# Precision_ATMega32U4.net
KiCad netlist of a schematic drawn in EAGLE
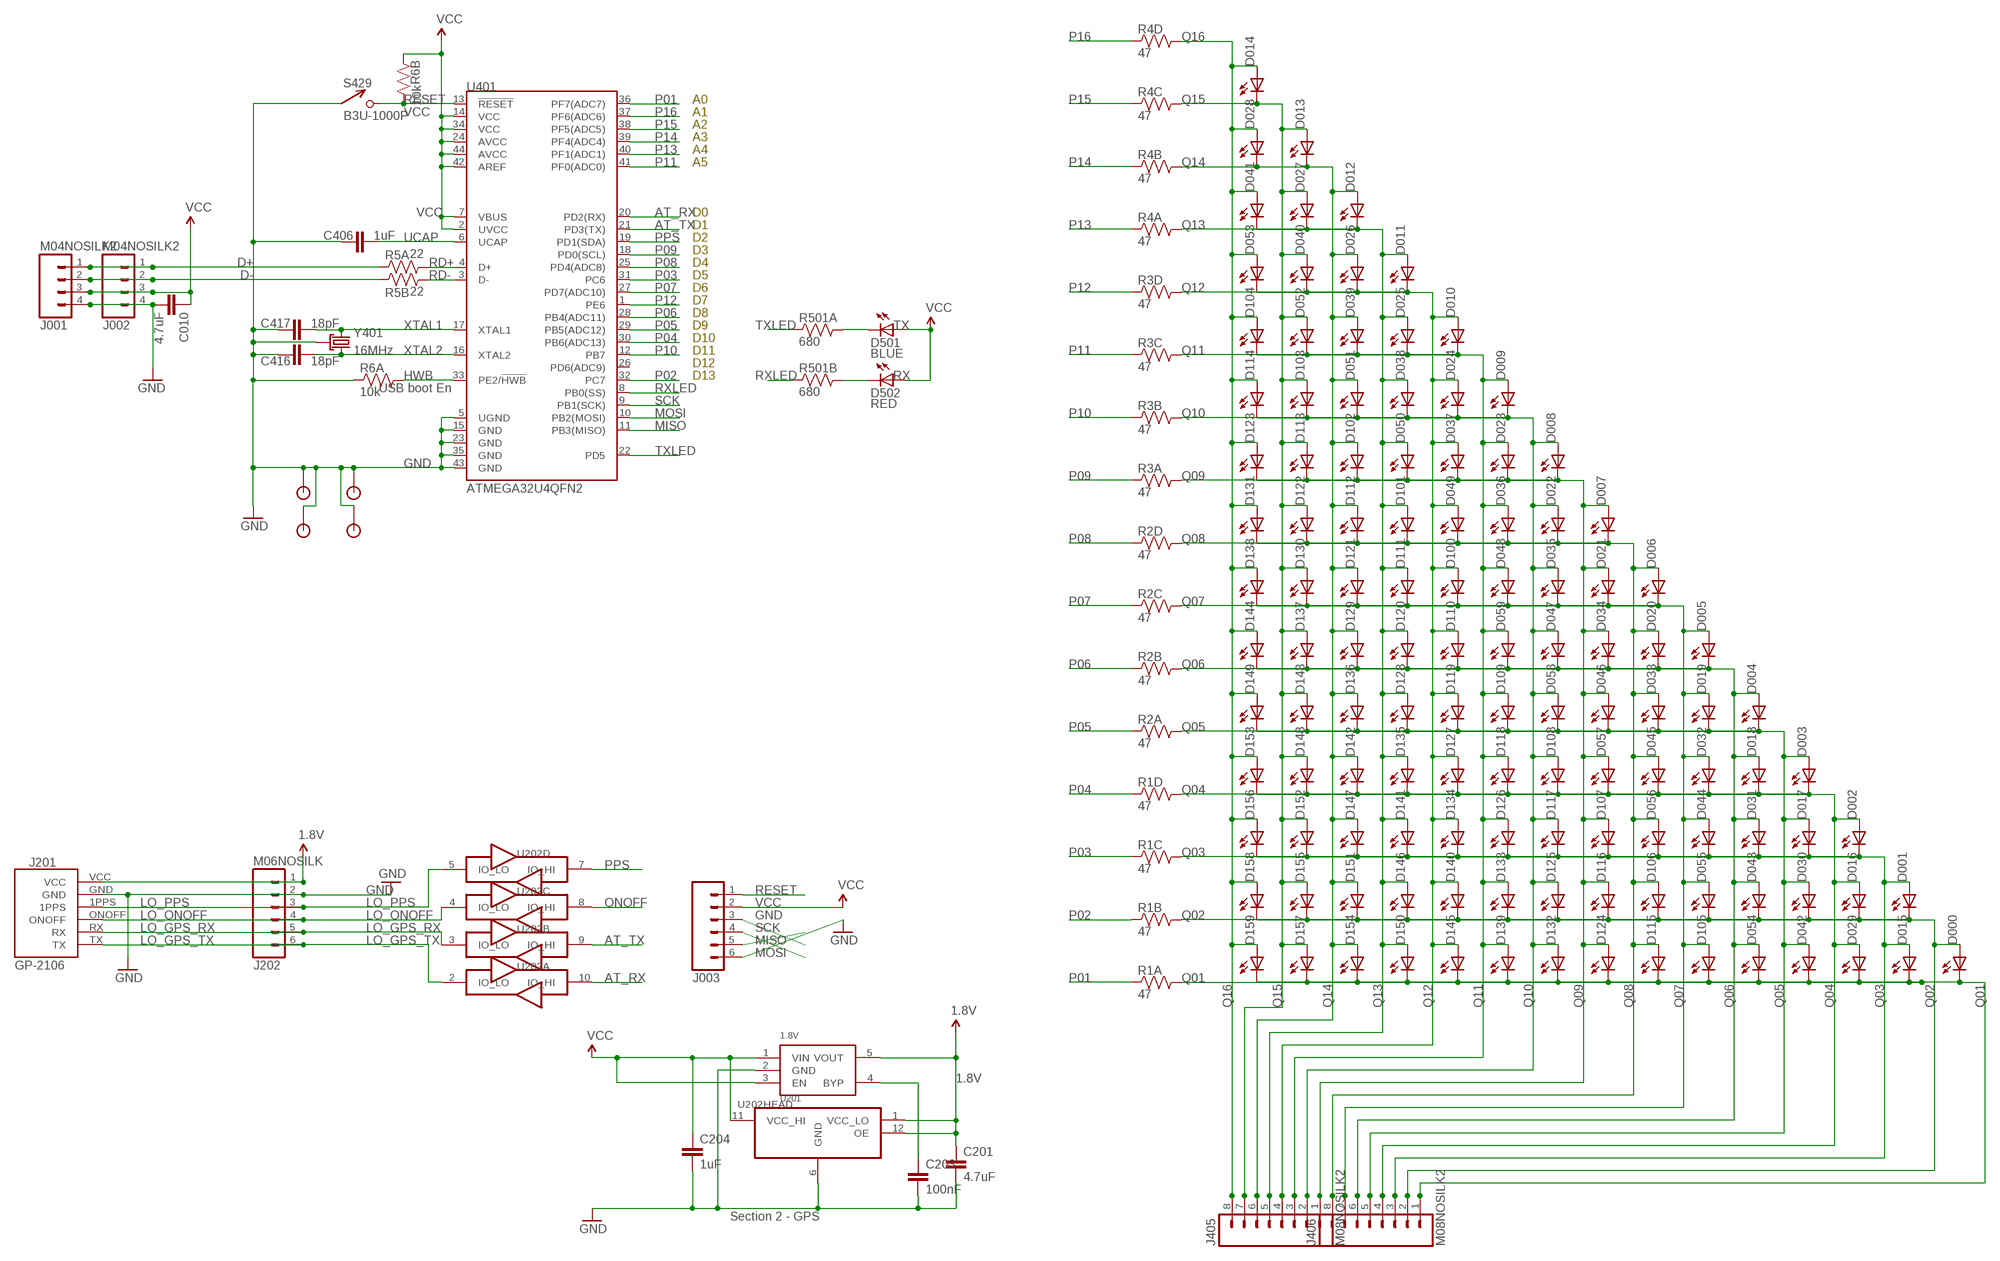
[diagram p0: schematic, sheet 1]

(export (version "E")
  (design (tool "Eeschema 10.0.6"))
  (components
    (comp (ref "C010")
      (value "4.7uF")
      (footprint "eagle-import:0603-CAP")
      (libsource (lib "eagle-import") (part "CAP0603-CAP"))
    )
    (comp (ref "C201")
      (value "4.7uF")
      (footprint "eagle-import:0603-CAP")
      (libsource (lib "eagle-import") (part "SparkFun-Passives_CAP0603-CAP"))
    )
    (comp (ref "C203")
      (value "100nF")
      (footprint "eagle-import:0603-CAP")
      (libsource (lib "eagle-import") (part "SparkFun-Passives_CAP0603-CAP"))
    )
    (comp (ref "C204")
      (value "1uF")
      (footprint "eagle-import:0603-CAP")
      (libsource (lib "eagle-import") (part "SparkFun-Passives_CAP0603-CAP"))
    )
    (comp (ref "C406")
      (value "1uF")
      (footprint "eagle-import:0603-CAP")
      (libsource (lib "eagle-import") (part "CAP0603-CAP"))
    )
    (comp (ref "C416")
      (value "18pF")
      (footprint "eagle-import:0603-CAP")
      (libsource (lib "eagle-import") (part "CAP0603-CAP"))
    )
    (comp (ref "C417")
      (value "18pF")
      (footprint "eagle-import:0603-CAP")
      (libsource (lib "eagle-import") (part "CAP0603-CAP"))
    )
    (comp (ref "D000")
      (value "HOUR")
      (footprint "eagle-import:LED-0603")
      (libsource (lib "eagle-import") (part "LED0603"))
    )
    (comp (ref "D001")
      (value "HOUR")
      (footprint "eagle-import:LED-0603")
      (libsource (lib "eagle-import") (part "LED0603"))
    )
    (comp (ref "D002")
      (value "HOUR")
      (footprint "eagle-import:LED-0603")
      (libsource (lib "eagle-import") (part "LED0603"))
    )
    (comp (ref "D003")
      (value "HOUR")
      (footprint "eagle-import:LED-0603")
      (libsource (lib "eagle-import") (part "LED0603"))
    )
    (comp (ref "D004")
      (value "HOUR")
      (footprint "eagle-import:LED-0603")
      (libsource (lib "eagle-import") (part "LED0603"))
    )
    (comp (ref "D005")
      (value "HOUR")
      (footprint "eagle-import:LED-0603")
      (libsource (lib "eagle-import") (part "LED0603"))
    )
    (comp (ref "D006")
      (value "HOUR")
      (footprint "eagle-import:LED-0603")
      (libsource (lib "eagle-import") (part "LED0603"))
    )
    (comp (ref "D007")
      (value "HOUR")
      (footprint "eagle-import:LED-0603")
      (libsource (lib "eagle-import") (part "LED0603"))
    )
    (comp (ref "D008")
      (value "HOUR")
      (footprint "eagle-import:LED-0603")
      (libsource (lib "eagle-import") (part "LED0603"))
    )
    (comp (ref "D009")
      (value "HOUR")
      (footprint "eagle-import:LED-0603")
      (libsource (lib "eagle-import") (part "LED0603"))
    )
    (comp (ref "D010")
      (value "HOUR")
      (footprint "eagle-import:LED-0603")
      (libsource (lib "eagle-import") (part "LED0603"))
    )
    (comp (ref "D011")
      (value "HOUR")
      (footprint "eagle-import:LED-0603")
      (libsource (lib "eagle-import") (part "LED0603"))
    )
    (comp (ref "D012")
      (value "HOUR")
      (footprint "eagle-import:LED-0603")
      (libsource (lib "eagle-import") (part "LED0603"))
    )
    (comp (ref "D013")
      (value "HOUR")
      (footprint "eagle-import:LED-0603")
      (libsource (lib "eagle-import") (part "LED0603"))
    )
    (comp (ref "D014")
      (value "HOUR")
      (footprint "eagle-import:LED-0603")
      (libsource (lib "eagle-import") (part "LED0603"))
    )
    (comp (ref "D015")
      (value "HOUR")
      (footprint "eagle-import:LED-0603")
      (libsource (lib "eagle-import") (part "LED0603"))
    )
    (comp (ref "D016")
      (value "HOUR")
      (footprint "eagle-import:LED-0603")
      (libsource (lib "eagle-import") (part "LED0603"))
    )
    (comp (ref "D017")
      (value "HOUR")
      (footprint "eagle-import:LED-0603")
      (libsource (lib "eagle-import") (part "LED0603"))
    )
    (comp (ref "D018")
      (value "HOUR")
      (footprint "eagle-import:LED-0603")
      (libsource (lib "eagle-import") (part "LED0603"))
    )
    (comp (ref "D019")
      (value "HOUR")
      (footprint "eagle-import:LED-0603")
      (libsource (lib "eagle-import") (part "LED0603"))
    )
    (comp (ref "D020")
      (value "HOUR")
      (footprint "eagle-import:LED-0603")
      (libsource (lib "eagle-import") (part "LED0603"))
    )
    (comp (ref "D021")
      (value "HOUR")
      (footprint "eagle-import:LED-0603")
      (libsource (lib "eagle-import") (part "LED0603"))
    )
    (comp (ref "D022")
      (value "HOUR")
      (footprint "eagle-import:LED-0603")
      (libsource (lib "eagle-import") (part "LED0603"))
    )
    (comp (ref "D023")
      (value "HOUR")
      (footprint "eagle-import:LED-0603")
      (libsource (lib "eagle-import") (part "LED0603"))
    )
    (comp (ref "D024")
      (value "HOUR")
      (footprint "eagle-import:LED-0603")
      (libsource (lib "eagle-import") (part "LED0603"))
    )
    (comp (ref "D025")
      (value "HOUR")
      (footprint "eagle-import:LED-0603")
      (libsource (lib "eagle-import") (part "LED0603"))
    )
    (comp (ref "D026")
      (value "HOUR")
      (footprint "eagle-import:LED-0603")
      (libsource (lib "eagle-import") (part "LED0603"))
    )
    (comp (ref "D027")
      (value "HOUR")
      (footprint "eagle-import:LED-0603")
      (libsource (lib "eagle-import") (part "LED0603"))
    )
    (comp (ref "D028")
      (value "HOUR")
      (footprint "eagle-import:LED-0603")
      (libsource (lib "eagle-import") (part "LED0603"))
    )
    (comp (ref "D029")
      (value "HOUR")
      (footprint "eagle-import:LED-0603")
      (libsource (lib "eagle-import") (part "LED0603"))
    )
    (comp (ref "D030")
      (value "HOUR")
      (footprint "eagle-import:LED-0603")
      (libsource (lib "eagle-import") (part "LED0603"))
    )
    (comp (ref "D031")
      (value "HOUR")
      (footprint "eagle-import:LED-0603")
      (libsource (lib "eagle-import") (part "LED0603"))
    )
    (comp (ref "D032")
      (value "HOUR")
      (footprint "eagle-import:LED-0603")
      (libsource (lib "eagle-import") (part "LED0603"))
    )
    (comp (ref "D033")
      (value "HOUR")
      (footprint "eagle-import:LED-0603")
      (libsource (lib "eagle-import") (part "LED0603"))
    )
    (comp (ref "D034")
      (value "HOUR")
      (footprint "eagle-import:LED-0603")
      (libsource (lib "eagle-import") (part "LED0603"))
    )
    (comp (ref "D035")
      (value "HOUR")
      (footprint "eagle-import:LED-0603")
      (libsource (lib "eagle-import") (part "LED0603"))
    )
    (comp (ref "D036")
      (value "HOUR")
      (footprint "eagle-import:LED-0603")
      (libsource (lib "eagle-import") (part "LED0603"))
    )
    (comp (ref "D037")
      (value "HOUR")
      (footprint "eagle-import:LED-0603")
      (libsource (lib "eagle-import") (part "LED0603"))
    )
    (comp (ref "D038")
      (value "HOUR")
      (footprint "eagle-import:LED-0603")
      (libsource (lib "eagle-import") (part "LED0603"))
    )
    (comp (ref "D039")
      (value "HOUR")
      (footprint "eagle-import:LED-0603")
      (libsource (lib "eagle-import") (part "LED0603"))
    )
    (comp (ref "D040")
      (value "HOUR")
      (footprint "eagle-import:LED-0603")
      (libsource (lib "eagle-import") (part "LED0603"))
    )
    (comp (ref "D041")
      (value "HOUR")
      (footprint "eagle-import:LED-0603")
      (libsource (lib "eagle-import") (part "LED0603"))
    )
    (comp (ref "D042")
      (value "HOUR")
      (footprint "eagle-import:LED-0603")
      (libsource (lib "eagle-import") (part "LED0603"))
    )
    (comp (ref "D043")
      (value "HOUR")
      (footprint "eagle-import:LED-0603")
      (libsource (lib "eagle-import") (part "LED0603"))
    )
    (comp (ref "D044")
      (value "HOUR")
      (footprint "eagle-import:LED-0603")
      (libsource (lib "eagle-import") (part "LED0603"))
    )
    (comp (ref "D045")
      (value "HOUR")
      (footprint "eagle-import:LED-0603")
      (libsource (lib "eagle-import") (part "LED0603"))
    )
    (comp (ref "D046")
      (value "HOUR")
      (footprint "eagle-import:LED-0603")
      (libsource (lib "eagle-import") (part "LED0603"))
    )
    (comp (ref "D047")
      (value "HOUR")
      (footprint "eagle-import:LED-0603")
      (libsource (lib "eagle-import") (part "LED0603"))
    )
    (comp (ref "D048")
      (value "HOUR")
      (footprint "eagle-import:LED-0603")
      (libsource (lib "eagle-import") (part "LED0603"))
    )
    (comp (ref "D049")
      (value "HOUR")
      (footprint "eagle-import:LED-0603")
      (libsource (lib "eagle-import") (part "LED0603"))
    )
    (comp (ref "D050")
      (value "HOUR")
      (footprint "eagle-import:LED-0603")
      (libsource (lib "eagle-import") (part "LED0603"))
    )
    (comp (ref "D051")
      (value "HOUR")
      (footprint "eagle-import:LED-0603")
      (libsource (lib "eagle-import") (part "LED0603"))
    )
    (comp (ref "D052")
      (value "HOUR")
      (footprint "eagle-import:LED-0603")
      (libsource (lib "eagle-import") (part "LED0603"))
    )
    (comp (ref "D053")
      (value "HOUR")
      (footprint "eagle-import:LED-0603")
      (libsource (lib "eagle-import") (part "LED0603"))
    )
    (comp (ref "D054")
      (value "HOUR")
      (footprint "eagle-import:LED-0603")
      (libsource (lib "eagle-import") (part "LED0603"))
    )
    (comp (ref "D055")
      (value "HOUR")
      (footprint "eagle-import:LED-0603")
      (libsource (lib "eagle-import") (part "LED0603"))
    )
    (comp (ref "D056")
      (value "HOUR")
      (footprint "eagle-import:LED-0603")
      (libsource (lib "eagle-import") (part "LED0603"))
    )
    (comp (ref "D057")
      (value "HOUR")
      (footprint "eagle-import:LED-0603")
      (libsource (lib "eagle-import") (part "LED0603"))
    )
    (comp (ref "D058")
      (value "HOUR")
      (footprint "eagle-import:LED-0603")
      (libsource (lib "eagle-import") (part "LED0603"))
    )
    (comp (ref "D059")
      (value "HOUR")
      (footprint "eagle-import:LED-0603")
      (libsource (lib "eagle-import") (part "LED0603"))
    )
    (comp (ref "D100")
      (value "HOUR")
      (footprint "eagle-import:LED-0603")
      (libsource (lib "eagle-import") (part "LED0603"))
    )
    (comp (ref "D101")
      (value "HOUR")
      (footprint "eagle-import:LED-0603")
      (libsource (lib "eagle-import") (part "LED0603"))
    )
    (comp (ref "D102")
      (value "HOUR")
      (footprint "eagle-import:LED-0603")
      (libsource (lib "eagle-import") (part "LED0603"))
    )
    (comp (ref "D103")
      (value "HOUR")
      (footprint "eagle-import:LED-0603")
      (libsource (lib "eagle-import") (part "LED0603"))
    )
    (comp (ref "D104")
      (value "HOUR")
      (footprint "eagle-import:LED-0603")
      (libsource (lib "eagle-import") (part "LED0603"))
    )
    (comp (ref "D105")
      (value "HOUR")
      (footprint "eagle-import:LED-0603")
      (libsource (lib "eagle-import") (part "LED0603"))
    )
    (comp (ref "D106")
      (value "HOUR")
      (footprint "eagle-import:LED-0603")
      (libsource (lib "eagle-import") (part "LED0603"))
    )
    (comp (ref "D107")
      (value "HOUR")
      (footprint "eagle-import:LED-0603")
      (libsource (lib "eagle-import") (part "LED0603"))
    )
    (comp (ref "D108")
      (value "HOUR")
      (footprint "eagle-import:LED-0603")
      (libsource (lib "eagle-import") (part "LED0603"))
    )
    (comp (ref "D109")
      (value "HOUR")
      (footprint "eagle-import:LED-0603")
      (libsource (lib "eagle-import") (part "LED0603"))
    )
    (comp (ref "D110")
      (value "HOUR")
      (footprint "eagle-import:LED-0603")
      (libsource (lib "eagle-import") (part "LED0603"))
    )
    (comp (ref "D111")
      (value "HOUR")
      (footprint "eagle-import:LED-0603")
      (libsource (lib "eagle-import") (part "LED0603"))
    )
    (comp (ref "D112")
      (value "HOUR")
      (footprint "eagle-import:LED-0603")
      (libsource (lib "eagle-import") (part "LED0603"))
    )
    (comp (ref "D113")
      (value "HOUR")
      (footprint "eagle-import:LED-0603")
      (libsource (lib "eagle-import") (part "LED0603"))
    )
    (comp (ref "D114")
      (value "HOUR")
      (footprint "eagle-import:LED-0603")
      (libsource (lib "eagle-import") (part "LED0603"))
    )
    (comp (ref "D115")
      (value "HOUR")
      (footprint "eagle-import:LED-0603")
      (libsource (lib "eagle-import") (part "LED0603"))
    )
    (comp (ref "D116")
      (value "HOUR")
      (footprint "eagle-import:LED-0603")
      (libsource (lib "eagle-import") (part "LED0603"))
    )
    (comp (ref "D117")
      (value "HOUR")
      (footprint "eagle-import:LED-0603")
      (libsource (lib "eagle-import") (part "LED0603"))
    )
    (comp (ref "D118")
      (value "HOUR")
      (footprint "eagle-import:LED-0603")
      (libsource (lib "eagle-import") (part "LED0603"))
    )
    (comp (ref "D119")
      (value "HOUR")
      (footprint "eagle-import:LED-0603")
      (libsource (lib "eagle-import") (part "LED0603"))
    )
    (comp (ref "D120")
      (value "HOUR")
      (footprint "eagle-import:LED-0603")
      (libsource (lib "eagle-import") (part "LED0603"))
    )
    (comp (ref "D121")
      (value "HOUR")
      (footprint "eagle-import:LED-0603")
      (libsource (lib "eagle-import") (part "LED0603"))
    )
    (comp (ref "D122")
      (value "HOUR")
      (footprint "eagle-import:LED-0603")
      (libsource (lib "eagle-import") (part "LED0603"))
    )
    (comp (ref "D123")
      (value "HOUR")
      (footprint "eagle-import:LED-0603")
      (libsource (lib "eagle-import") (part "LED0603"))
    )
    (comp (ref "D124")
      (value "HOUR")
      (footprint "eagle-import:LED-0603")
      (libsource (lib "eagle-import") (part "LED0603"))
    )
    (comp (ref "D125")
      (value "HOUR")
      (footprint "eagle-import:LED-0603")
      (libsource (lib "eagle-import") (part "LED0603"))
    )
    (comp (ref "D126")
      (value "HOUR")
      (footprint "eagle-import:LED-0603")
      (libsource (lib "eagle-import") (part "LED0603"))
    )
    (comp (ref "D127")
      (value "HOUR")
      (footprint "eagle-import:LED-0603")
      (libsource (lib "eagle-import") (part "LED0603"))
    )
    (comp (ref "D128")
      (value "HOUR")
      (footprint "eagle-import:LED-0603")
      (libsource (lib "eagle-import") (part "LED0603"))
    )
    (comp (ref "D129")
      (value "HOUR")
      (footprint "eagle-import:LED-0603")
      (libsource (lib "eagle-import") (part "LED0603"))
    )
    (comp (ref "D130")
      (value "HOUR")
      (footprint "eagle-import:LED-0603")
      (libsource (lib "eagle-import") (part "LED0603"))
    )
    (comp (ref "D131")
      (value "HOUR")
      (footprint "eagle-import:LED-0603")
      (libsource (lib "eagle-import") (part "LED0603"))
    )
    (comp (ref "D132")
      (value "HOUR")
      (footprint "eagle-import:LED-0603")
      (libsource (lib "eagle-import") (part "LED0603"))
    )
    (comp (ref "D133")
      (value "HOUR")
      (footprint "eagle-import:LED-0603")
      (libsource (lib "eagle-import") (part "LED0603"))
    )
    (comp (ref "D134")
      (value "HOUR")
      (footprint "eagle-import:LED-0603")
      (libsource (lib "eagle-import") (part "LED0603"))
    )
    (comp (ref "D135")
      (value "HOUR")
      (footprint "eagle-import:LED-0603")
      (libsource (lib "eagle-import") (part "LED0603"))
    )
    (comp (ref "D136")
      (value "HOUR")
      (footprint "eagle-import:LED-0603")
      (libsource (lib "eagle-import") (part "LED0603"))
    )
    (comp (ref "D137")
      (value "HOUR")
      (footprint "eagle-import:LED-0603")
      (libsource (lib "eagle-import") (part "LED0603"))
    )
    (comp (ref "D138")
      (value "HOUR")
      (footprint "eagle-import:LED-0603")
      (libsource (lib "eagle-import") (part "LED0603"))
    )
    (comp (ref "D139")
      (value "HOUR")
      (footprint "eagle-import:LED-0603")
      (libsource (lib "eagle-import") (part "LED0603"))
    )
    (comp (ref "D140")
      (value "HOUR")
      (footprint "eagle-import:LED-0603")
      (libsource (lib "eagle-import") (part "LED0603"))
    )
    (comp (ref "D141")
      (value "HOUR")
      (footprint "eagle-import:LED-0603")
      (libsource (lib "eagle-import") (part "LED0603"))
    )
    (comp (ref "D142")
      (value "HOUR")
      (footprint "eagle-import:LED-0603")
      (libsource (lib "eagle-import") (part "LED0603"))
    )
    (comp (ref "D143")
      (value "HOUR")
      (footprint "eagle-import:LED-0603")
      (libsource (lib "eagle-import") (part "LED0603"))
    )
    (comp (ref "D144")
      (value "HOUR")
      (footprint "eagle-import:LED-0603")
      (libsource (lib "eagle-import") (part "LED0603"))
    )
    (comp (ref "D145")
      (value "HOUR")
      (footprint "eagle-import:LED-0603")
      (libsource (lib "eagle-import") (part "LED0603"))
    )
    (comp (ref "D146")
      (value "HOUR")
      (footprint "eagle-import:LED-0603")
      (libsource (lib "eagle-import") (part "LED0603"))
    )
    (comp (ref "D147")
      (value "HOUR")
      (footprint "eagle-import:LED-0603")
      (libsource (lib "eagle-import") (part "LED0603"))
    )
    (comp (ref "D148")
      (value "HOUR")
      (footprint "eagle-import:LED-0603")
      (libsource (lib "eagle-import") (part "LED0603"))
    )
    (comp (ref "D149")
      (value "HOUR")
      (footprint "eagle-import:LED-0603")
      (libsource (lib "eagle-import") (part "LED0603"))
    )
    (comp (ref "D150")
      (value "HOUR")
      (footprint "eagle-import:LED-0603")
      (libsource (lib "eagle-import") (part "LED0603"))
    )
    (comp (ref "D151")
      (value "HOUR")
      (footprint "eagle-import:LED-0603")
      (libsource (lib "eagle-import") (part "LED0603"))
    )
    (comp (ref "D152")
      (value "HOUR")
      (footprint "eagle-import:LED-0603")
      (libsource (lib "eagle-import") (part "LED0603"))
    )
    (comp (ref "D153")
      (value "HOUR")
      (footprint "eagle-import:LED-0603")
      (libsource (lib "eagle-import") (part "LED0603"))
    )
    (comp (ref "D154")
      (value "HOUR")
      (footprint "eagle-import:LED-0603")
      (libsource (lib "eagle-import") (part "LED0603"))
    )
    (comp (ref "D155")
      (value "HOUR")
      (footprint "eagle-import:LED-0603")
      (libsource (lib "eagle-import") (part "LED0603"))
    )
    (comp (ref "D156")
      (value "HOUR")
      (footprint "eagle-import:LED-0603")
      (libsource (lib "eagle-import") (part "LED0603"))
    )
    (comp (ref "D157")
      (value "HOUR")
      (footprint "eagle-import:LED-0603")
      (libsource (lib "eagle-import") (part "LED0603"))
    )
    (comp (ref "D158")
      (value "HOUR")
      (footprint "eagle-import:LED-0603")
      (libsource (lib "eagle-import") (part "LED0603"))
    )
    (comp (ref "D159")
      (value "HOUR")
      (footprint "eagle-import:LED-0603")
      (libsource (lib "eagle-import") (part "LED0603"))
    )
    (comp (ref "D501")
      (value "BLUE")
      (footprint "eagle-import:LED-0603")
      (libsource (lib "eagle-import") (part "LED0603"))
    )
    (comp (ref "D502")
      (value "RED")
      (footprint "eagle-import:LED-0603")
      (libsource (lib "eagle-import") (part "LED0603"))
    )
    (comp (ref "J001")
      (value "M04NOSILK2")
      (footprint "eagle-import:1X04")
      (libsource (lib "eagle-import") (part "M04NOSILK2"))
    )
    (comp (ref "J002")
      (value "M04NOSILK2")
      (footprint "eagle-import:1X04")
      (libsource (lib "eagle-import") (part "M04NOSILK2"))
    )
    (comp (ref "J003")
      (value "M06SIP")
      (footprint "eagle-import:1X06")
      (libsource (lib "eagle-import") (part "M06SIP"))
    )
    (comp (ref "J201")
      (value "GP-2106")
      (footprint "eagle-import:GP-2106")
      (libsource (lib "eagle-import") (part "GP-2106"))
    )
    (comp (ref "J202")
      (value "M06NOSILK")
      (footprint "eagle-import:M06SIP")
      (libsource (lib "eagle-import") (part "M06NOSILK"))
    )
    (comp (ref "J405")
      (value "M08NOSILK2")
      (footprint "eagle-import:1X08")
      (libsource (lib "eagle-import") (part "M08NOSILK2"))
    )
    (comp (ref "J406")
      (value "M08NOSILK2")
      (footprint "eagle-import:1X08")
      (libsource (lib "eagle-import") (part "M08NOSILK2"))
    )
    (comp (ref "JP1")
      (value "STANDOFF")
      (footprint "eagle-import:STANDOFF")
      (libsource (lib "eagle-import") (part "STANDOFF"))
    )
    (comp (ref "JP2")
      (value "STANDOFF")
      (footprint "eagle-import:STANDOFF")
      (libsource (lib "eagle-import") (part "STANDOFF"))
    )
    (comp (ref "JP3")
      (value "STANDOFF")
      (footprint "eagle-import:STANDOFF")
      (libsource (lib "eagle-import") (part "STANDOFF"))
    )
    (comp (ref "JP4")
      (value "STANDOFF")
      (footprint "eagle-import:STANDOFF")
      (libsource (lib "eagle-import") (part "STANDOFF"))
    )
    (comp (ref "R1")
      (value "47")
      (footprint "eagle-import:CRA04")
      (libsource (lib "eagle-import") (part "RP404"))
    )
    (comp (ref "R2")
      (value "47")
      (footprint "eagle-import:CRA04")
      (libsource (lib "eagle-import") (part "RP404"))
    )
    (comp (ref "R3")
      (value "47")
      (footprint "eagle-import:CRA04")
      (libsource (lib "eagle-import") (part "RP404"))
    )
    (comp (ref "R4")
      (value "47")
      (footprint "eagle-import:CRA04")
      (libsource (lib "eagle-import") (part "RP404"))
    )
    (comp (ref "R5")
      (value "22")
      (footprint "eagle-import:CRA02")
      (libsource (lib "eagle-import") (part "RP2EXB24V"))
    )
    (comp (ref "R6")
      (value "10k")
      (footprint "eagle-import:CRA02")
      (libsource (lib "eagle-import") (part "RP2EXB24V"))
    )
    (comp (ref "R501")
      (value "680")
      (footprint "eagle-import:CRA02")
      (libsource (lib "eagle-import") (part "RP2EXB24V"))
    )
    (comp (ref "S429")
      (value "B3U-1000P")
      (footprint "eagle-import:B3U-1000P")
      (libsource (lib "eagle-import") (part "B3U-1000P"))
    )
    (comp (ref "U201")
      (value "1.8V")
      (footprint "eagle-import:SOT-23-5")
      (libsource (lib "eagle-import") (part "MIC5319D5"))
    )
    (comp (ref "U202")
      (value "TXB0104RUT")
      (footprint "eagle-import:R-PUQFN-N12")
      (libsource (lib "eagle-import") (part "TXB0104RUT"))
    )
    (comp (ref "U401")
      (value "ATMEGA32U4QFN2")
      (footprint "eagle-import:SPARKFUN-DIGITALIC_QFN-44-NOPAD")
      (libsource (lib "eagle-import") (part "ATMEGA32U4QFN2"))
    )
    (comp (ref "Y401")
      (value "16MHz")
      (footprint "eagle-import:CRYSTAL_SMD")
      (libsource (lib "eagle-import") (part "TSX-3225"))
    )
  )
  (nets
    (net (code "1") (name "/AT_RX") (class "Default")
      (node (ref "U202") (pin "10") (pinfunction "IO_HI_10") (pintype "bidirectional"))
      (node (ref "U401") (pin "20") (pinfunction "PD2(RX)_20") (pintype "bidirectional"))
    )
    (net (code "2") (name "/AT_TX") (class "Default")
      (node (ref "U202") (pin "9") (pinfunction "IO_HI_9") (pintype "bidirectional"))
      (node (ref "U401") (pin "21") (pinfunction "PD3(TX)_21") (pintype "bidirectional"))
    )
    (net (code "3") (name "/D+") (class "Default")
      (node (ref "J001") (pin "1") (pinfunction "1_1") (pintype "passive"))
      (node (ref "J002") (pin "1") (pinfunction "1_1") (pintype "passive"))
      (node (ref "R5") (pin "1") (pinfunction "1_1") (pintype "passive"))
    )
    (net (code "4") (name "/D-") (class "Default")
      (node (ref "J001") (pin "2") (pinfunction "2_2") (pintype "passive"))
      (node (ref "J002") (pin "2") (pinfunction "2_2") (pintype "passive"))
      (node (ref "R5") (pin "2") (pinfunction "1_2") (pintype "passive"))
    )
    (net (code "5") (name "/HWB") (class "Default")
      (node (ref "R6") (pin "4") (pinfunction "2_4") (pintype "passive"))
      (node (ref "U401") (pin "33") (pinfunction "PE2/~{HWB}_33") (pintype "bidirectional"))
    )
    (net (code "6") (name "/LO_GPS_RX") (class "Default")
      (node (ref "J201") (pin "RX") (pinfunction "RX_RX") (pintype "bidirectional"))
      (node (ref "J202") (pin "5") (pinfunction "5_5") (pintype "passive"))
      (node (ref "U202") (pin "3") (pinfunction "IO_LO_3") (pintype "bidirectional"))
    )
    (net (code "7") (name "/LO_GPS_TX") (class "Default")
      (node (ref "J201") (pin "TX") (pinfunction "TX_TX") (pintype "bidirectional"))
      (node (ref "J202") (pin "6") (pinfunction "6_6") (pintype "passive"))
      (node (ref "U202") (pin "2") (pinfunction "IO_LO_2") (pintype "bidirectional"))
    )
    (net (code "8") (name "/LO_ONOFF") (class "Default")
      (node (ref "J201") (pin "ONOFF") (pinfunction "ONOFF_ONOFF") (pintype "bidirectional"))
      (node (ref "J202") (pin "4") (pinfunction "4_4") (pintype "passive"))
      (node (ref "U202") (pin "4") (pinfunction "IO_LO_4") (pintype "bidirectional"))
    )
    (net (code "9") (name "/LO_PPS") (class "Default")
      (node (ref "J201") (pin "1PPS") (pinfunction "1PPS_1PPS") (pintype "bidirectional"))
      (node (ref "J202") (pin "3") (pinfunction "3_3") (pintype "passive"))
      (node (ref "U202") (pin "5") (pinfunction "IO_LO_5") (pintype "bidirectional"))
    )
    (net (code "10") (name "/MISO") (class "Default")
      (node (ref "J003") (pin "3") (pinfunction "3_3") (pintype "passive"))
      (node (ref "U401") (pin "11") (pinfunction "PB3(MISO)_11") (pintype "bidirectional"))
    )
    (net (code "11") (name "/MOSI") (class "Default")
      (node (ref "J003") (pin "4") (pinfunction "4_4") (pintype "passive"))
      (node (ref "U401") (pin "10") (pinfunction "PB2(MOSI)_10") (pintype "bidirectional"))
    )
    (net (code "12") (name "/ONOFF") (class "Default")
      (node (ref "U202") (pin "8") (pinfunction "IO_HI_8") (pintype "bidirectional"))
    )
    (net (code "13") (name "/P01") (class "Default")
      (node (ref "R1") (pin "1") (pinfunction "1_1") (pintype "passive"))
      (node (ref "U401") (pin "36") (pinfunction "PF7(ADC7)_36") (pintype "bidirectional"))
    )
    (net (code "14") (name "/P02") (class "Default")
      (node (ref "R1") (pin "2") (pinfunction "1_2") (pintype "passive"))
      (node (ref "U401") (pin "32") (pinfunction "PC7_32") (pintype "bidirectional"))
    )
    (net (code "15") (name "/P03") (class "Default")
      (node (ref "R1") (pin "3") (pinfunction "1_3") (pintype "passive"))
      (node (ref "U401") (pin "31") (pinfunction "PC6_31") (pintype "bidirectional"))
    )
    (net (code "16") (name "/P04") (class "Default")
      (node (ref "R1") (pin "4") (pinfunction "1_4") (pintype "passive"))
      (node (ref "U401") (pin "30") (pinfunction "PB6(ADC13)_30") (pintype "bidirectional"))
    )
    (net (code "17") (name "/P05") (class "Default")
      (node (ref "R2") (pin "1") (pinfunction "1_1") (pintype "passive"))
      (node (ref "U401") (pin "29") (pinfunction "PB5(ADC12)_29") (pintype "bidirectional"))
    )
    (net (code "18") (name "/P06") (class "Default")
      (node (ref "R2") (pin "2") (pinfunction "1_2") (pintype "passive"))
      (node (ref "U401") (pin "28") (pinfunction "PB4(ADC11)_28") (pintype "bidirectional"))
    )
    (net (code "19") (name "/P07") (class "Default")
      (node (ref "R2") (pin "3") (pinfunction "1_3") (pintype "passive"))
      (node (ref "U401") (pin "27") (pinfunction "PD7(ADC10)_27") (pintype "bidirectional"))
    )
    (net (code "20") (name "/P08") (class "Default")
      (node (ref "R2") (pin "4") (pinfunction "1_4") (pintype "passive"))
      (node (ref "U401") (pin "25") (pinfunction "PD4(ADC8)_25") (pintype "bidirectional"))
    )
    (net (code "21") (name "/P09") (class "Default")
      (node (ref "R3") (pin "1") (pinfunction "1_1") (pintype "passive"))
      (node (ref "U401") (pin "18") (pinfunction "PD0(SCL)_18") (pintype "bidirectional"))
    )
    (net (code "22") (name "/P10") (class "Default")
      (node (ref "R3") (pin "2") (pinfunction "1_2") (pintype "passive"))
      (node (ref "U401") (pin "12") (pinfunction "PB7_12") (pintype "bidirectional"))
    )
    (net (code "23") (name "/P11") (class "Default")
      (node (ref "R3") (pin "3") (pinfunction "1_3") (pintype "passive"))
      (node (ref "U401") (pin "41") (pinfunction "PF0(ADC0)_41") (pintype "bidirectional"))
    )
    (net (code "24") (name "/P12") (class "Default")
      (node (ref "R3") (pin "4") (pinfunction "1_4") (pintype "passive"))
      (node (ref "U401") (pin "1") (pinfunction "PE6_1") (pintype "bidirectional"))
    )
    (net (code "25") (name "/P13") (class "Default")
      (node (ref "R4") (pin "1") (pinfunction "1_1") (pintype "passive"))
      (node (ref "U401") (pin "40") (pinfunction "PF1(ADC1)_40") (pintype "bidirectional"))
    )
    (net (code "26") (name "/P14") (class "Default")
      (node (ref "R4") (pin "2") (pinfunction "1_2") (pintype "passive"))
      (node (ref "U401") (pin "39") (pinfunction "PF4(ADC4)_39") (pintype "bidirectional"))
    )
    (net (code "27") (name "/P15") (class "Default")
      (node (ref "R4") (pin "3") (pinfunction "1_3") (pintype "passive"))
      (node (ref "U401") (pin "38") (pinfunction "PF5(ADC5)_38") (pintype "bidirectional"))
    )
    (net (code "28") (name "/P16") (class "Default")
      (node (ref "R4") (pin "4") (pinfunction "1_4") (pintype "passive"))
      (node (ref "U401") (pin "37") (pinfunction "PF6(ADC6)_37") (pintype "bidirectional"))
    )
    (net (code "29") (name "/PPS") (class "Default")
      (node (ref "U202") (pin "7") (pinfunction "IO_HI_7") (pintype "bidirectional"))
      (node (ref "U401") (pin "19") (pinfunction "PD1(SDA)_19") (pintype "bidirectional"))
    )
    (net (code "30") (name "/Q01") (class "Default")
      (node (ref "D000") (pin "C") (pinfunction "C_C") (pintype "passive"))
      (node (ref "D015") (pin "C") (pinfunction "C_C") (pintype "passive"))
      (node (ref "D029") (pin "C") (pinfunction "C_C") (pintype "passive"))
      (node (ref "D042") (pin "C") (pinfunction "C_C") (pintype "passive"))
      (node (ref "D054") (pin "C") (pinfunction "C_C") (pintype "passive"))
      (node (ref "D105") (pin "C") (pinfunction "C_C") (pintype "passive"))
      (node (ref "D115") (pin "C") (pinfunction "C_C") (pintype "passive"))
      (node (ref "D124") (pin "C") (pinfunction "C_C") (pintype "passive"))
      (node (ref "D132") (pin "C") (pinfunction "C_C") (pintype "passive"))
      (node (ref "D139") (pin "C") (pinfunction "C_C") (pintype "passive"))
      (node (ref "D145") (pin "C") (pinfunction "C_C") (pintype "passive"))
      (node (ref "D150") (pin "C") (pinfunction "C_C") (pintype "passive"))
      (node (ref "D154") (pin "C") (pinfunction "C_C") (pintype "passive"))
      (node (ref "D157") (pin "C") (pinfunction "C_C") (pintype "passive"))
      (node (ref "D159") (pin "C") (pinfunction "C_C") (pintype "passive"))
      (node (ref "J406") (pin "1") (pinfunction "1_1") (pintype "passive"))
      (node (ref "R1") (pin "8") (pinfunction "2_8") (pintype "passive"))
    )
    (net (code "31") (name "/Q02") (class "Default")
      (node (ref "D000") (pin "A") (pinfunction "A_A") (pintype "passive"))
      (node (ref "D001") (pin "C") (pinfunction "C_C") (pintype "passive"))
      (node (ref "D016") (pin "C") (pinfunction "C_C") (pintype "passive"))
      (node (ref "D030") (pin "C") (pinfunction "C_C") (pintype "passive"))
      (node (ref "D043") (pin "C") (pinfunction "C_C") (pintype "passive"))
      (node (ref "D055") (pin "C") (pinfunction "C_C") (pintype "passive"))
      (node (ref "D106") (pin "C") (pinfunction "C_C") (pintype "passive"))
      (node (ref "D116") (pin "C") (pinfunction "C_C") (pintype "passive"))
      (node (ref "D125") (pin "C") (pinfunction "C_C") (pintype "passive"))
      (node (ref "D133") (pin "C") (pinfunction "C_C") (pintype "passive"))
      (node (ref "D140") (pin "C") (pinfunction "C_C") (pintype "passive"))
      (node (ref "D146") (pin "C") (pinfunction "C_C") (pintype "passive"))
      (node (ref "D151") (pin "C") (pinfunction "C_C") (pintype "passive"))
      (node (ref "D155") (pin "C") (pinfunction "C_C") (pintype "passive"))
      (node (ref "D158") (pin "C") (pinfunction "C_C") (pintype "passive"))
      (node (ref "J406") (pin "2") (pinfunction "2_2") (pintype "passive"))
      (node (ref "R1") (pin "7") (pinfunction "2_7") (pintype "passive"))
    )
    (net (code "32") (name "/Q03") (class "Default")
      (node (ref "D001") (pin "A") (pinfunction "A_A") (pintype "passive"))
      (node (ref "D002") (pin "C") (pinfunction "C_C") (pintype "passive"))
      (node (ref "D015") (pin "A") (pinfunction "A_A") (pintype "passive"))
      (node (ref "D017") (pin "C") (pinfunction "C_C") (pintype "passive"))
      (node (ref "D031") (pin "C") (pinfunction "C_C") (pintype "passive"))
      (node (ref "D044") (pin "C") (pinfunction "C_C") (pintype "passive"))
      (node (ref "D056") (pin "C") (pinfunction "C_C") (pintype "passive"))
      (node (ref "D107") (pin "C") (pinfunction "C_C") (pintype "passive"))
      (node (ref "D117") (pin "C") (pinfunction "C_C") (pintype "passive"))
      (node (ref "D126") (pin "C") (pinfunction "C_C") (pintype "passive"))
      (node (ref "D134") (pin "C") (pinfunction "C_C") (pintype "passive"))
      (node (ref "D141") (pin "C") (pinfunction "C_C") (pintype "passive"))
      (node (ref "D147") (pin "C") (pinfunction "C_C") (pintype "passive"))
      (node (ref "D152") (pin "C") (pinfunction "C_C") (pintype "passive"))
      (node (ref "D156") (pin "C") (pinfunction "C_C") (pintype "passive"))
      (node (ref "J406") (pin "3") (pinfunction "3_3") (pintype "passive"))
      (node (ref "R1") (pin "6") (pinfunction "2_6") (pintype "passive"))
    )
    (net (code "33") (name "/Q04") (class "Default")
      (node (ref "D002") (pin "A") (pinfunction "A_A") (pintype "passive"))
      (node (ref "D003") (pin "C") (pinfunction "C_C") (pintype "passive"))
      (node (ref "D016") (pin "A") (pinfunction "A_A") (pintype "passive"))
      (node (ref "D018") (pin "C") (pinfunction "C_C") (pintype "passive"))
      (node (ref "D029") (pin "A") (pinfunction "A_A") (pintype "passive"))
      (node (ref "D032") (pin "C") (pinfunction "C_C") (pintype "passive"))
      (node (ref "D045") (pin "C") (pinfunction "C_C") (pintype "passive"))
      (node (ref "D057") (pin "C") (pinfunction "C_C") (pintype "passive"))
      (node (ref "D108") (pin "C") (pinfunction "C_C") (pintype "passive"))
      (node (ref "D118") (pin "C") (pinfunction "C_C") (pintype "passive"))
      (node (ref "D127") (pin "C") (pinfunction "C_C") (pintype "passive"))
      (node (ref "D135") (pin "C") (pinfunction "C_C") (pintype "passive"))
      (node (ref "D142") (pin "C") (pinfunction "C_C") (pintype "passive"))
      (node (ref "D148") (pin "C") (pinfunction "C_C") (pintype "passive"))
      (node (ref "D153") (pin "C") (pinfunction "C_C") (pintype "passive"))
      (node (ref "J406") (pin "4") (pinfunction "4_4") (pintype "passive"))
      (node (ref "R1") (pin "5") (pinfunction "2_5") (pintype "passive"))
    )
    (net (code "34") (name "/Q05") (class "Default")
      (node (ref "D003") (pin "A") (pinfunction "A_A") (pintype "passive"))
      (node (ref "D004") (pin "C") (pinfunction "C_C") (pintype "passive"))
      (node (ref "D017") (pin "A") (pinfunction "A_A") (pintype "passive"))
      (node (ref "D019") (pin "C") (pinfunction "C_C") (pintype "passive"))
      (node (ref "D030") (pin "A") (pinfunction "A_A") (pintype "passive"))
      (node (ref "D033") (pin "C") (pinfunction "C_C") (pintype "passive"))
      (node (ref "D042") (pin "A") (pinfunction "A_A") (pintype "passive"))
      (node (ref "D046") (pin "C") (pinfunction "C_C") (pintype "passive"))
      (node (ref "D058") (pin "C") (pinfunction "C_C") (pintype "passive"))
      (node (ref "D109") (pin "C") (pinfunction "C_C") (pintype "passive"))
      (node (ref "D119") (pin "C") (pinfunction "C_C") (pintype "passive"))
      (node (ref "D128") (pin "C") (pinfunction "C_C") (pintype "passive"))
      (node (ref "D136") (pin "C") (pinfunction "C_C") (pintype "passive"))
      (node (ref "D143") (pin "C") (pinfunction "C_C") (pintype "passive"))
      (node (ref "D149") (pin "C") (pinfunction "C_C") (pintype "passive"))
      (node (ref "J406") (pin "5") (pinfunction "5_5") (pintype "passive"))
      (node (ref "R2") (pin "8") (pinfunction "2_8") (pintype "passive"))
    )
    (net (code "35") (name "/Q06") (class "Default")
      (node (ref "D004") (pin "A") (pinfunction "A_A") (pintype "passive"))
      (node (ref "D005") (pin "C") (pinfunction "C_C") (pintype "passive"))
      (node (ref "D018") (pin "A") (pinfunction "A_A") (pintype "passive"))
      (node (ref "D020") (pin "C") (pinfunction "C_C") (pintype "passive"))
      (node (ref "D031") (pin "A") (pinfunction "A_A") (pintype "passive"))
      (node (ref "D034") (pin "C") (pinfunction "C_C") (pintype "passive"))
      (node (ref "D043") (pin "A") (pinfunction "A_A") (pintype "passive"))
      (node (ref "D047") (pin "C") (pinfunction "C_C") (pintype "passive"))
      (node (ref "D054") (pin "A") (pinfunction "A_A") (pintype "passive"))
      (node (ref "D059") (pin "C") (pinfunction "C_C") (pintype "passive"))
      (node (ref "D110") (pin "C") (pinfunction "C_C") (pintype "passive"))
      (node (ref "D120") (pin "C") (pinfunction "C_C") (pintype "passive"))
      (node (ref "D129") (pin "C") (pinfunction "C_C") (pintype "passive"))
      (node (ref "D137") (pin "C") (pinfunction "C_C") (pintype "passive"))
      (node (ref "D144") (pin "C") (pinfunction "C_C") (pintype "passive"))
      (node (ref "J406") (pin "6") (pinfunction "6_6") (pintype "passive"))
      (node (ref "R2") (pin "7") (pinfunction "2_7") (pintype "passive"))
    )
    (net (code "36") (name "/Q07") (class "Default")
      (node (ref "D005") (pin "A") (pinfunction "A_A") (pintype "passive"))
      (node (ref "D006") (pin "C") (pinfunction "C_C") (pintype "passive"))
      (node (ref "D019") (pin "A") (pinfunction "A_A") (pintype "passive"))
      (node (ref "D021") (pin "C") (pinfunction "C_C") (pintype "passive"))
      (node (ref "D032") (pin "A") (pinfunction "A_A") (pintype "passive"))
      (node (ref "D035") (pin "C") (pinfunction "C_C") (pintype "passive"))
      (node (ref "D044") (pin "A") (pinfunction "A_A") (pintype "passive"))
      (node (ref "D048") (pin "C") (pinfunction "C_C") (pintype "passive"))
      (node (ref "D055") (pin "A") (pinfunction "A_A") (pintype "passive"))
      (node (ref "D100") (pin "C") (pinfunction "C_C") (pintype "passive"))
      (node (ref "D105") (pin "A") (pinfunction "A_A") (pintype "passive"))
      (node (ref "D111") (pin "C") (pinfunction "C_C") (pintype "passive"))
      (node (ref "D121") (pin "C") (pinfunction "C_C") (pintype "passive"))
      (node (ref "D130") (pin "C") (pinfunction "C_C") (pintype "passive"))
      (node (ref "D138") (pin "C") (pinfunction "C_C") (pintype "passive"))
      (node (ref "J406") (pin "7") (pinfunction "7_7") (pintype "passive"))
      (node (ref "R2") (pin "6") (pinfunction "2_6") (pintype "passive"))
    )
    (net (code "37") (name "/Q08") (class "Default")
      (node (ref "D006") (pin "A") (pinfunction "A_A") (pintype "passive"))
      (node (ref "D007") (pin "C") (pinfunction "C_C") (pintype "passive"))
      (node (ref "D020") (pin "A") (pinfunction "A_A") (pintype "passive"))
      (node (ref "D022") (pin "C") (pinfunction "C_C") (pintype "passive"))
      (node (ref "D033") (pin "A") (pinfunction "A_A") (pintype "passive"))
      (node (ref "D036") (pin "C") (pinfunction "C_C") (pintype "passive"))
      (node (ref "D045") (pin "A") (pinfunction "A_A") (pintype "passive"))
      (node (ref "D049") (pin "C") (pinfunction "C_C") (pintype "passive"))
      (node (ref "D056") (pin "A") (pinfunction "A_A") (pintype "passive"))
      (node (ref "D101") (pin "C") (pinfunction "C_C") (pintype "passive"))
      (node (ref "D106") (pin "A") (pinfunction "A_A") (pintype "passive"))
      (node (ref "D112") (pin "C") (pinfunction "C_C") (pintype "passive"))
      (node (ref "D115") (pin "A") (pinfunction "A_A") (pintype "passive"))
      (node (ref "D122") (pin "C") (pinfunction "C_C") (pintype "passive"))
      (node (ref "D131") (pin "C") (pinfunction "C_C") (pintype "passive"))
      (node (ref "J406") (pin "8") (pinfunction "8_8") (pintype "passive"))
      (node (ref "R2") (pin "5") (pinfunction "2_5") (pintype "passive"))
    )
    (net (code "38") (name "/Q09") (class "Default")
      (node (ref "D007") (pin "A") (pinfunction "A_A") (pintype "passive"))
      (node (ref "D008") (pin "C") (pinfunction "C_C") (pintype "passive"))
      (node (ref "D021") (pin "A") (pinfunction "A_A") (pintype "passive"))
      (node (ref "D023") (pin "C") (pinfunction "C_C") (pintype "passive"))
      (node (ref "D034") (pin "A") (pinfunction "A_A") (pintype "passive"))
      (node (ref "D037") (pin "C") (pinfunction "C_C") (pintype "passive"))
      (node (ref "D046") (pin "A") (pinfunction "A_A") (pintype "passive"))
      (node (ref "D050") (pin "C") (pinfunction "C_C") (pintype "passive"))
      (node (ref "D057") (pin "A") (pinfunction "A_A") (pintype "passive"))
      (node (ref "D102") (pin "C") (pinfunction "C_C") (pintype "passive"))
      (node (ref "D107") (pin "A") (pinfunction "A_A") (pintype "passive"))
      (node (ref "D113") (pin "C") (pinfunction "C_C") (pintype "passive"))
      (node (ref "D116") (pin "A") (pinfunction "A_A") (pintype "passive"))
      (node (ref "D123") (pin "C") (pinfunction "C_C") (pintype "passive"))
      (node (ref "D124") (pin "A") (pinfunction "A_A") (pintype "passive"))
      (node (ref "J405") (pin "1") (pinfunction "1_1") (pintype "passive"))
      (node (ref "R3") (pin "8") (pinfunction "2_8") (pintype "passive"))
    )
    (net (code "39") (name "/Q10") (class "Default")
      (node (ref "D008") (pin "A") (pinfunction "A_A") (pintype "passive"))
      (node (ref "D009") (pin "C") (pinfunction "C_C") (pintype "passive"))
      (node (ref "D022") (pin "A") (pinfunction "A_A") (pintype "passive"))
      (node (ref "D024") (pin "C") (pinfunction "C_C") (pintype "passive"))
      (node (ref "D035") (pin "A") (pinfunction "A_A") (pintype "passive"))
      (node (ref "D038") (pin "C") (pinfunction "C_C") (pintype "passive"))
      (node (ref "D047") (pin "A") (pinfunction "A_A") (pintype "passive"))
      (node (ref "D051") (pin "C") (pinfunction "C_C") (pintype "passive"))
      (node (ref "D058") (pin "A") (pinfunction "A_A") (pintype "passive"))
      (node (ref "D103") (pin "C") (pinfunction "C_C") (pintype "passive"))
      (node (ref "D108") (pin "A") (pinfunction "A_A") (pintype "passive"))
      (node (ref "D114") (pin "C") (pinfunction "C_C") (pintype "passive"))
      (node (ref "D117") (pin "A") (pinfunction "A_A") (pintype "passive"))
      (node (ref "D125") (pin "A") (pinfunction "A_A") (pintype "passive"))
      (node (ref "D132") (pin "A") (pinfunction "A_A") (pintype "passive"))
      (node (ref "J405") (pin "2") (pinfunction "2_2") (pintype "passive"))
      (node (ref "R3") (pin "7") (pinfunction "2_7") (pintype "passive"))
    )
    (net (code "40") (name "/Q11") (class "Default")
      (node (ref "D009") (pin "A") (pinfunction "A_A") (pintype "passive"))
      (node (ref "D010") (pin "C") (pinfunction "C_C") (pintype "passive"))
      (node (ref "D023") (pin "A") (pinfunction "A_A") (pintype "passive"))
      (node (ref "D025") (pin "C") (pinfunction "C_C") (pintype "passive"))
      (node (ref "D036") (pin "A") (pinfunction "A_A") (pintype "passive"))
      (node (ref "D039") (pin "C") (pinfunction "C_C") (pintype "passive"))
      (node (ref "D048") (pin "A") (pinfunction "A_A") (pintype "passive"))
      (node (ref "D052") (pin "C") (pinfunction "C_C") (pintype "passive"))
      (node (ref "D059") (pin "A") (pinfunction "A_A") (pintype "passive"))
      (node (ref "D104") (pin "C") (pinfunction "C_C") (pintype "passive"))
      (node (ref "D109") (pin "A") (pinfunction "A_A") (pintype "passive"))
      (node (ref "D118") (pin "A") (pinfunction "A_A") (pintype "passive"))
      (node (ref "D126") (pin "A") (pinfunction "A_A") (pintype "passive"))
      (node (ref "D133") (pin "A") (pinfunction "A_A") (pintype "passive"))
      (node (ref "D139") (pin "A") (pinfunction "A_A") (pintype "passive"))
      (node (ref "J405") (pin "3") (pinfunction "3_3") (pintype "passive"))
      (node (ref "R3") (pin "6") (pinfunction "2_6") (pintype "passive"))
    )
    (net (code "41") (name "/Q12") (class "Default")
      (node (ref "D010") (pin "A") (pinfunction "A_A") (pintype "passive"))
      (node (ref "D011") (pin "C") (pinfunction "C_C") (pintype "passive"))
      (node (ref "D024") (pin "A") (pinfunction "A_A") (pintype "passive"))
      (node (ref "D026") (pin "C") (pinfunction "C_C") (pintype "passive"))
      (node (ref "D037") (pin "A") (pinfunction "A_A") (pintype "passive"))
      (node (ref "D040") (pin "C") (pinfunction "C_C") (pintype "passive"))
      (node (ref "D049") (pin "A") (pinfunction "A_A") (pintype "passive"))
      (node (ref "D053") (pin "C") (pinfunction "C_C") (pintype "passive"))
      (node (ref "D100") (pin "A") (pinfunction "A_A") (pintype "passive"))
      (node (ref "D110") (pin "A") (pinfunction "A_A") (pintype "passive"))
      (node (ref "D119") (pin "A") (pinfunction "A_A") (pintype "passive"))
      (node (ref "D127") (pin "A") (pinfunction "A_A") (pintype "passive"))
      (node (ref "D134") (pin "A") (pinfunction "A_A") (pintype "passive"))
      (node (ref "D140") (pin "A") (pinfunction "A_A") (pintype "passive"))
      (node (ref "D145") (pin "A") (pinfunction "A_A") (pintype "passive"))
      (node (ref "J405") (pin "4") (pinfunction "4_4") (pintype "passive"))
      (node (ref "R3") (pin "5") (pinfunction "2_5") (pintype "passive"))
    )
    (net (code "42") (name "/Q13") (class "Default")
      (node (ref "D011") (pin "A") (pinfunction "A_A") (pintype "passive"))
      (node (ref "D012") (pin "C") (pinfunction "C_C") (pintype "passive"))
      (node (ref "D025") (pin "A") (pinfunction "A_A") (pintype "passive"))
      (node (ref "D027") (pin "C") (pinfunction "C_C") (pintype "passive"))
      (node (ref "D038") (pin "A") (pinfunction "A_A") (pintype "passive"))
      (node (ref "D041") (pin "C") (pinfunction "C_C") (pintype "passive"))
      (node (ref "D050") (pin "A") (pinfunction "A_A") (pintype "passive"))
      (node (ref "D101") (pin "A") (pinfunction "A_A") (pintype "passive"))
      (node (ref "D111") (pin "A") (pinfunction "A_A") (pintype "passive"))
      (node (ref "D120") (pin "A") (pinfunction "A_A") (pintype "passive"))
      (node (ref "D128") (pin "A") (pinfunction "A_A") (pintype "passive"))
      (node (ref "D135") (pin "A") (pinfunction "A_A") (pintype "passive"))
      (node (ref "D141") (pin "A") (pinfunction "A_A") (pintype "passive"))
      (node (ref "D146") (pin "A") (pinfunction "A_A") (pintype "passive"))
      (node (ref "D150") (pin "A") (pinfunction "A_A") (pintype "passive"))
      (node (ref "J405") (pin "5") (pinfunction "5_5") (pintype "passive"))
      (node (ref "R4") (pin "8") (pinfunction "2_8") (pintype "passive"))
    )
    (net (code "43") (name "/Q14") (class "Default")
      (node (ref "D012") (pin "A") (pinfunction "A_A") (pintype "passive"))
      (node (ref "D013") (pin "C") (pinfunction "C_C") (pintype "passive"))
      (node (ref "D026") (pin "A") (pinfunction "A_A") (pintype "passive"))
      (node (ref "D028") (pin "C") (pinfunction "C_C") (pintype "passive"))
      (node (ref "D039") (pin "A") (pinfunction "A_A") (pintype "passive"))
      (node (ref "D051") (pin "A") (pinfunction "A_A") (pintype "passive"))
      (node (ref "D102") (pin "A") (pinfunction "A_A") (pintype "passive"))
      (node (ref "D112") (pin "A") (pinfunction "A_A") (pintype "passive"))
      (node (ref "D121") (pin "A") (pinfunction "A_A") (pintype "passive"))
      (node (ref "D129") (pin "A") (pinfunction "A_A") (pintype "passive"))
      (node (ref "D136") (pin "A") (pinfunction "A_A") (pintype "passive"))
      (node (ref "D142") (pin "A") (pinfunction "A_A") (pintype "passive"))
      (node (ref "D147") (pin "A") (pinfunction "A_A") (pintype "passive"))
      (node (ref "D151") (pin "A") (pinfunction "A_A") (pintype "passive"))
      (node (ref "D154") (pin "A") (pinfunction "A_A") (pintype "passive"))
      (node (ref "J405") (pin "6") (pinfunction "6_6") (pintype "passive"))
      (node (ref "R4") (pin "7") (pinfunction "2_7") (pintype "passive"))
    )
    (net (code "44") (name "/Q15") (class "Default")
      (node (ref "D013") (pin "A") (pinfunction "A_A") (pintype "passive"))
      (node (ref "D014") (pin "C") (pinfunction "C_C") (pintype "passive"))
      (node (ref "D027") (pin "A") (pinfunction "A_A") (pintype "passive"))
      (node (ref "D040") (pin "A") (pinfunction "A_A") (pintype "passive"))
      (node (ref "D052") (pin "A") (pinfunction "A_A") (pintype "passive"))
      (node (ref "D103") (pin "A") (pinfunction "A_A") (pintype "passive"))
      (node (ref "D113") (pin "A") (pinfunction "A_A") (pintype "passive"))
      (node (ref "D122") (pin "A") (pinfunction "A_A") (pintype "passive"))
      (node (ref "D130") (pin "A") (pinfunction "A_A") (pintype "passive"))
      (node (ref "D137") (pin "A") (pinfunction "A_A") (pintype "passive"))
      (node (ref "D143") (pin "A") (pinfunction "A_A") (pintype "passive"))
      (node (ref "D148") (pin "A") (pinfunction "A_A") (pintype "passive"))
      (node (ref "D152") (pin "A") (pinfunction "A_A") (pintype "passive"))
      (node (ref "D155") (pin "A") (pinfunction "A_A") (pintype "passive"))
      (node (ref "D157") (pin "A") (pinfunction "A_A") (pintype "passive"))
      (node (ref "J405") (pin "7") (pinfunction "7_7") (pintype "passive"))
      (node (ref "R4") (pin "6") (pinfunction "2_6") (pintype "passive"))
    )
    (net (code "45") (name "/Q16") (class "Default")
      (node (ref "D014") (pin "A") (pinfunction "A_A") (pintype "passive"))
      (node (ref "D028") (pin "A") (pinfunction "A_A") (pintype "passive"))
      (node (ref "D041") (pin "A") (pinfunction "A_A") (pintype "passive"))
      (node (ref "D053") (pin "A") (pinfunction "A_A") (pintype "passive"))
      (node (ref "D104") (pin "A") (pinfunction "A_A") (pintype "passive"))
      (node (ref "D114") (pin "A") (pinfunction "A_A") (pintype "passive"))
      (node (ref "D123") (pin "A") (pinfunction "A_A") (pintype "passive"))
      (node (ref "D131") (pin "A") (pinfunction "A_A") (pintype "passive"))
      (node (ref "D138") (pin "A") (pinfunction "A_A") (pintype "passive"))
      (node (ref "D144") (pin "A") (pinfunction "A_A") (pintype "passive"))
      (node (ref "D149") (pin "A") (pinfunction "A_A") (pintype "passive"))
      (node (ref "D153") (pin "A") (pinfunction "A_A") (pintype "passive"))
      (node (ref "D156") (pin "A") (pinfunction "A_A") (pintype "passive"))
      (node (ref "D158") (pin "A") (pinfunction "A_A") (pintype "passive"))
      (node (ref "D159") (pin "A") (pinfunction "A_A") (pintype "passive"))
      (node (ref "J405") (pin "8") (pinfunction "8_8") (pintype "passive"))
      (node (ref "R4") (pin "5") (pinfunction "2_5") (pintype "passive"))
    )
    (net (code "46") (name "/RD+") (class "Default")
      (node (ref "R5") (pin "4") (pinfunction "2_4") (pintype "passive"))
      (node (ref "U401") (pin "4") (pinfunction "D+_4") (pintype "bidirectional"))
    )
    (net (code "47") (name "/RD-") (class "Default")
      (node (ref "R5") (pin "3") (pinfunction "2_3") (pintype "passive"))
      (node (ref "U401") (pin "3") (pinfunction "D-_3") (pintype "bidirectional"))
    )
    (net (code "48") (name "/RESET") (class "Default")
      (node (ref "J003") (pin "1") (pinfunction "1_1") (pintype "passive"))
      (node (ref "R6") (pin "3") (pinfunction "2_3") (pintype "passive"))
      (node (ref "S429") (pin "P$2") (pinfunction "2_P$2") (pintype "bidirectional"))
      (node (ref "U401") (pin "13") (pinfunction "~{RESET}_13") (pintype "bidirectional"))
    )
    (net (code "49") (name "/RXLED") (class "Default")
      (node (ref "R501") (pin "2") (pinfunction "1_2") (pintype "passive"))
      (node (ref "U401") (pin "8") (pinfunction "PB0(SS)_8") (pintype "bidirectional"))
    )
    (net (code "50") (name "/SCK") (class "Default")
      (node (ref "J003") (pin "5") (pinfunction "5_5") (pintype "passive"))
      (node (ref "U401") (pin "9") (pinfunction "PB1(SCK)_9") (pintype "bidirectional"))
    )
    (net (code "51") (name "/TXLED") (class "Default")
      (node (ref "R501") (pin "1") (pinfunction "1_1") (pintype "passive"))
      (node (ref "U401") (pin "22") (pinfunction "PD5_22") (pintype "bidirectional"))
    )
    (net (code "52") (name "/UCAP") (class "Default")
      (node (ref "C406") (pin "1") (pinfunction "1_1") (pintype "passive"))
      (node (ref "U401") (pin "6") (pinfunction "UCAP_6") (pintype "bidirectional"))
    )
    (net (code "53") (name "/XTAL1") (class "Default")
      (node (ref "C417") (pin "2") (pinfunction "2_2") (pintype "passive"))
      (node (ref "U401") (pin "17") (pinfunction "XTAL1_17") (pintype "bidirectional"))
      (node (ref "Y401") (pin "1") (pinfunction "1_1") (pintype "passive"))
    )
    (net (code "54") (name "/XTAL2") (class "Default")
      (node (ref "C416") (pin "2") (pinfunction "2_2") (pintype "passive"))
      (node (ref "U401") (pin "16") (pinfunction "XTAL2_16") (pintype "bidirectional"))
      (node (ref "Y401") (pin "3") (pinfunction "2_3") (pintype "passive"))
    )
    (net (code "55") (name "1.8V") (class "Default")
      (node (ref "C201") (pin "1") (pinfunction "1_1") (pintype "passive"))
      (node (ref "J201") (pin "VCC") (pinfunction "VCC_VCC") (pintype "bidirectional"))
      (node (ref "J202") (pin "1") (pinfunction "1_1") (pintype "passive"))
      (node (ref "U201") (pin "5") (pinfunction "VOUT_5") (pintype "bidirectional"))
      (node (ref "U202") (pin "1") (pinfunction "VCC_LO_1") (pintype "power_in"))
      (node (ref "U202") (pin "12") (pinfunction "OE_12") (pintype "bidirectional"))
    )
    (net (code "56") (name "GND") (class "Default")
      (node (ref "C010") (pin "2") (pinfunction "2_2") (pintype "passive"))
      (node (ref "C201") (pin "2") (pinfunction "2_2") (pintype "passive"))
      (node (ref "C203") (pin "2") (pinfunction "2_2") (pintype "passive"))
      (node (ref "C204") (pin "2") (pinfunction "2_2") (pintype "passive"))
      (node (ref "C406") (pin "2") (pinfunction "2_2") (pintype "passive"))
      (node (ref "C416") (pin "1") (pinfunction "1_1") (pintype "passive"))
      (node (ref "C417") (pin "1") (pinfunction "1_1") (pintype "passive"))
      (node (ref "J001") (pin "4") (pinfunction "4_4") (pintype "passive"))
      (node (ref "J002") (pin "4") (pinfunction "4_4") (pintype "passive"))
      (node (ref "J003") (pin "6") (pinfunction "6_6") (pintype "passive"))
      (node (ref "J201") (pin "GND") (pinfunction "GND_GND") (pintype "bidirectional"))
      (node (ref "J202") (pin "2") (pinfunction "2_2") (pintype "passive"))
      (node (ref "JP1") (pin "P$1") (pinfunction "P$1_P$1") (pintype "bidirectional"))
      (node (ref "JP2") (pin "P$1") (pinfunction "P$1_P$1") (pintype "bidirectional"))
      (node (ref "JP3") (pin "P$1") (pinfunction "P$1_P$1") (pintype "bidirectional"))
      (node (ref "JP4") (pin "P$1") (pinfunction "P$1_P$1") (pintype "bidirectional"))
      (node (ref "R6") (pin "1") (pinfunction "1_1") (pintype "passive"))
      (node (ref "S429") (pin "P$1") (pinfunction "1_P$1") (pintype "bidirectional"))
      (node (ref "U201") (pin "2") (pinfunction "GND_2") (pintype "bidirectional"))
      (node (ref "U202") (pin "6") (pinfunction "GND_6") (pintype "power_in"))
      (node (ref "U401") (pin "15") (pinfunction "GND_15") (pintype "bidirectional"))
      (node (ref "U401") (pin "23") (pinfunction "GND_23") (pintype "bidirectional"))
      (node (ref "U401") (pin "35") (pinfunction "GND_35") (pintype "bidirectional"))
      (node (ref "U401") (pin "43") (pinfunction "GND_43") (pintype "bidirectional"))
      (node (ref "U401") (pin "5") (pinfunction "UGND_5") (pintype "bidirectional"))
      (node (ref "Y401") (pin "2") (pinfunction "GND_2") (pintype "passive"))
      (node (ref "Y401") (pin "4") (pinfunction "GND_4") (pintype "passive"))
    )
    (net (code "57") (name "Net-(R501A-2)") (class "Default")
      (node (ref "D501") (pin "C") (pinfunction "C_C") (pintype "passive"))
      (node (ref "R501") (pin "4") (pinfunction "2_4") (pintype "passive"))
    )
    (net (code "58") (name "Net-(R501B-2)") (class "Default")
      (node (ref "D502") (pin "C") (pinfunction "C_C") (pintype "passive"))
      (node (ref "R501") (pin "3") (pinfunction "2_3") (pintype "passive"))
    )
    (net (code "59") (name "Net-(U201-BYP)") (class "Default")
      (node (ref "C203") (pin "1") (pinfunction "1_1") (pintype "passive"))
      (node (ref "U201") (pin "4") (pinfunction "BYP_4") (pintype "bidirectional"))
    )
    (net (code "60") (name "VCC") (class "Default")
      (node (ref "C010") (pin "1") (pinfunction "1_1") (pintype "passive"))
      (node (ref "C204") (pin "1") (pinfunction "1_1") (pintype "passive"))
      (node (ref "D501") (pin "A") (pinfunction "A_A") (pintype "passive"))
      (node (ref "D502") (pin "A") (pinfunction "A_A") (pintype "passive"))
      (node (ref "J001") (pin "3") (pinfunction "3_3") (pintype "passive"))
      (node (ref "J002") (pin "3") (pinfunction "3_3") (pintype "passive"))
      (node (ref "J003") (pin "2") (pinfunction "2_2") (pintype "passive"))
      (node (ref "R6") (pin "2") (pinfunction "1_2") (pintype "passive"))
      (node (ref "U201") (pin "1") (pinfunction "VIN_1") (pintype "bidirectional"))
      (node (ref "U201") (pin "3") (pinfunction "EN_3") (pintype "bidirectional"))
      (node (ref "U202") (pin "11") (pinfunction "VCC_HI_11") (pintype "power_in"))
      (node (ref "U401") (pin "14") (pinfunction "VCC_14") (pintype "bidirectional"))
      (node (ref "U401") (pin "2") (pinfunction "UVCC_2") (pintype "bidirectional"))
      (node (ref "U401") (pin "24") (pinfunction "AVCC_24") (pintype "bidirectional"))
      (node (ref "U401") (pin "34") (pinfunction "VCC_34") (pintype "bidirectional"))
      (node (ref "U401") (pin "42") (pinfunction "AREF_42") (pintype "bidirectional"))
      (node (ref "U401") (pin "44") (pinfunction "AVCC_44") (pintype "bidirectional"))
      (node (ref "U401") (pin "7") (pinfunction "VBUS_7") (pintype "bidirectional"))
    )
    (net (code "61") (name "unconnected-(U401-PD6(ADC9)-Pad26)") (class "Default")
      (node (ref "U401") (pin "26") (pinfunction "PD6(ADC9)_26") (pintype "bidirectional"))
    )
  )
)
